# RF.net
KiCad netlist of a schematic drawn in Altium Designer
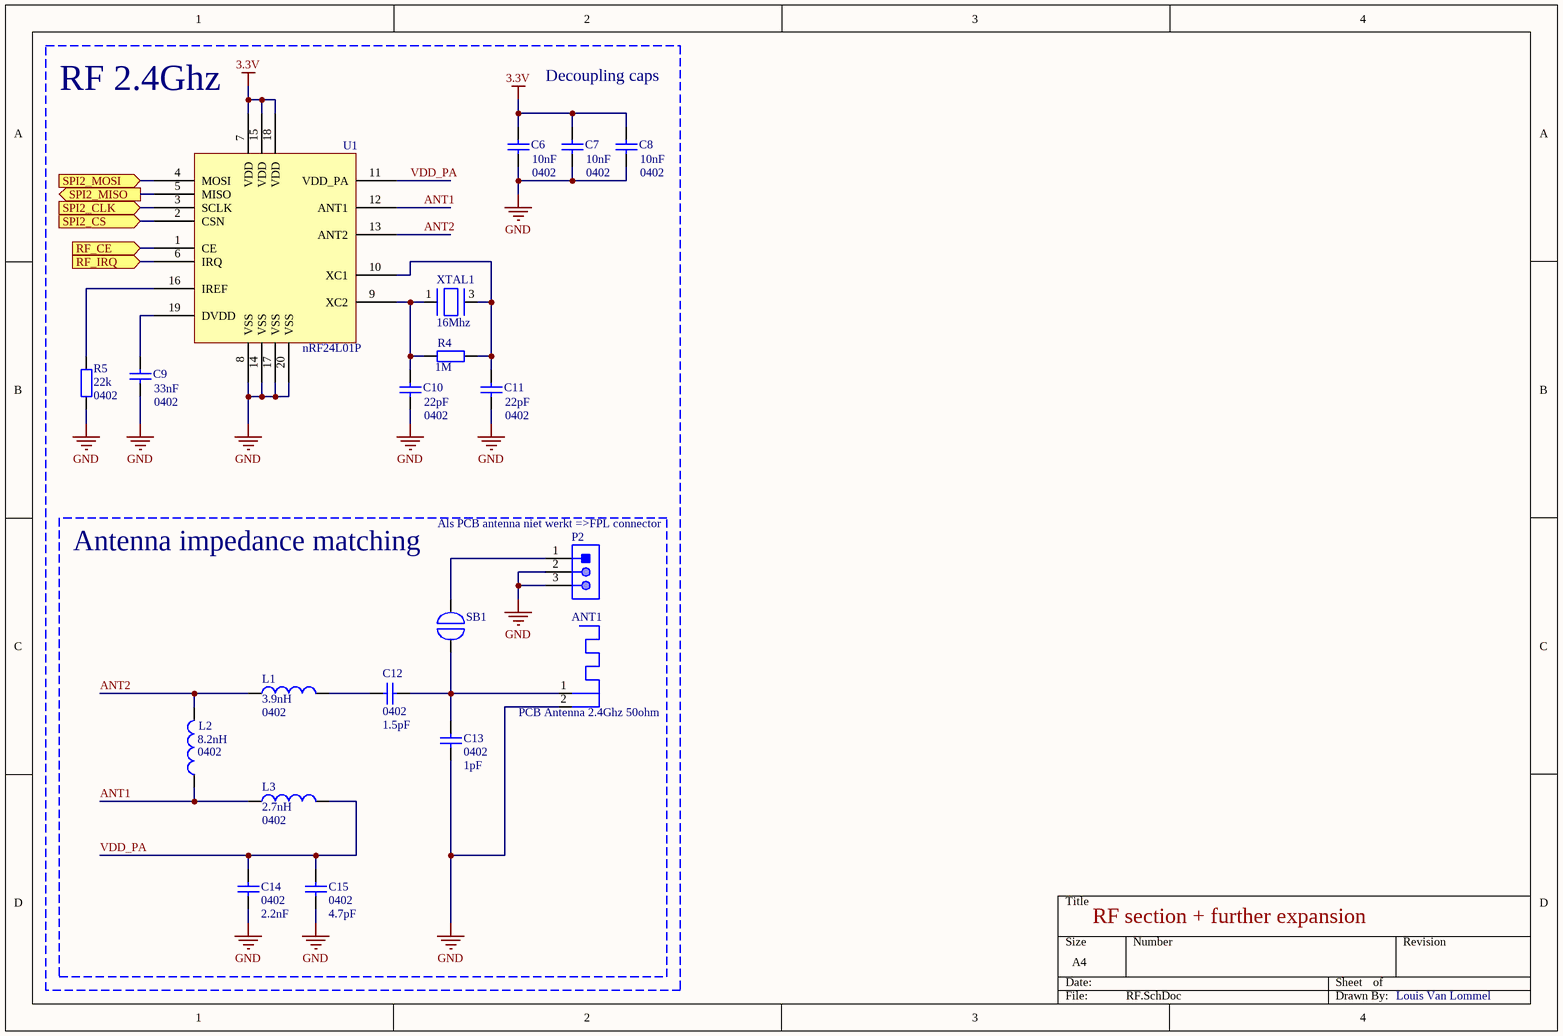
[diagram p0: RF.SchDoc]

(export (version "E")
  (design (tool "Eeschema 10.0.6"))
  (components
    (comp (ref "ANT1")
      (value "PCB Antenna 2.4Ghz 50ohm")
      (footprint "2.4Ghz Antenna")
      (libsource (lib "PE2_Schematics") (part "Antenna 2.4Ghz"))
    )
    (comp (ref "C6")
      (value "0402")
      (footprint "CAP_0402")
      (description "Capacitor")
      (fields (field (name "ALTIUM_VALUE") "10nF") (field (name "PUBLISHER") "Altium Limited"))
      (libsource (lib "Miscellaneous Devices") (part "Cap"))
    )
    (comp (ref "C7")
      (value "0402")
      (footprint "CAP_0402")
      (description "Capacitor")
      (fields (field (name "ALTIUM_VALUE") "10nF") (field (name "PUBLISHER") "Altium Limited"))
      (libsource (lib "Miscellaneous Devices") (part "Cap"))
    )
    (comp (ref "C8")
      (value "0402")
      (footprint "CAP_0402")
      (description "Capacitor")
      (fields (field (name "ALTIUM_VALUE") "10nF") (field (name "PUBLISHER") "Altium Limited"))
      (libsource (lib "Miscellaneous Devices") (part "Cap"))
    )
    (comp (ref "C9")
      (value "0402")
      (footprint "CAP_0402")
      (description "Capacitor")
      (fields (field (name "ALTIUM_VALUE") "33nF") (field (name "PUBLISHER") "Altium Limited"))
      (libsource (lib "Miscellaneous Devices") (part "Cap"))
    )
    (comp (ref "C10")
      (value "0402")
      (footprint "CAP_0402")
      (description "Capacitor")
      (fields (field (name "ALTIUM_VALUE") "22pF") (field (name "PUBLISHER") "Altium Limited"))
      (libsource (lib "Miscellaneous Devices") (part "Cap"))
    )
    (comp (ref "C11")
      (value "0402")
      (footprint "CAP_0402")
      (description "Capacitor")
      (fields (field (name "ALTIUM_VALUE") "22pF") (field (name "PUBLISHER") "Altium Limited"))
      (libsource (lib "Miscellaneous Devices") (part "Cap"))
    )
    (comp (ref "C12")
      (value "0402")
      (footprint "CAP_0402")
      (description "Capacitor")
      (fields (field (name "ALTIUM_VALUE") "1.5pF") (field (name "PUBLISHER") "Altium Limited"))
      (libsource (lib "Miscellaneous Devices") (part "Cap"))
    )
    (comp (ref "C13")
      (value "0402")
      (footprint "CAP_0402")
      (description "Capacitor")
      (fields (field (name "ALTIUM_VALUE") "1pF") (field (name "PUBLISHER") "Altium Limited"))
      (libsource (lib "Miscellaneous Devices") (part "Cap"))
    )
    (comp (ref "C14")
      (value "0402")
      (footprint "CAP_0402")
      (description "Capacitor")
      (fields (field (name "ALTIUM_VALUE") "2.2nF") (field (name "PUBLISHER") "Altium Limited"))
      (libsource (lib "Miscellaneous Devices") (part "Cap"))
    )
    (comp (ref "C15")
      (value "0402")
      (footprint "CAP_0402")
      (description "Capacitor")
      (fields (field (name "ALTIUM_VALUE") "4.7pF") (field (name "PUBLISHER") "Altium Limited"))
      (libsource (lib "Miscellaneous Devices") (part "Cap"))
    )
    (comp (ref "L1")
      (value "0402")
      (footprint "IND_0402")
      (description "Inductor")
      (fields (field (name "ALTIUM_VALUE") "3.9nH") (field (name "PUBLISHER") "Altium Limited"))
      (libsource (lib "Miscellaneous Devices") (part "Inductor"))
    )
    (comp (ref "L2")
      (value "0402")
      (footprint "IND_0402")
      (description "Inductor")
      (fields (field (name "ALTIUM_VALUE") "8.2nH") (field (name "PUBLISHER") "Altium Limited"))
      (libsource (lib "Miscellaneous Devices") (part "Inductor"))
    )
    (comp (ref "L3")
      (value "0402")
      (footprint "IND_0402")
      (description "Inductor")
      (fields (field (name "ALTIUM_VALUE") "2.7nH") (field (name "PUBLISHER") "Altium Limited"))
      (libsource (lib "Miscellaneous Devices") (part "Inductor"))
    )
    (comp (ref "P2")
      (value "~")
      (footprint "HRS-U.FL-R-SMT-3_V")
      (description "Ultra Small Coaxial Connector, 6 GHz, -40 to 90 degC, 3-Pin SMD, RoHS, Bulk")
      (fields (field (name "MANUFACTURER") "Hirose Electric"))
      (libsource (lib "Altium Content Vault") (part "CN-1P-M-R3"))
    )
    (comp (ref "R4")
      (value "1M")
      (footprint "RES_0402")
      (description "Resistor")
      (fields (field (name "PUBLISHER") "Altium Limited"))
      (libsource (lib "Miscellaneous Devices") (part "Res2"))
    )
    (comp (ref "R5")
      (value "0402")
      (footprint "RES_0603")
      (description "Resistor")
      (fields (field (name "ALTIUM_VALUE") "22k") (field (name "PUBLISHER") "Altium Limited"))
      (libsource (lib "") (part "Res2_1"))
    )
    (comp (ref "SB1")
      (value "~")
      (footprint "Solder bridge RF 0.254")
      (libsource (lib "PE2_Schematics") (part "Solder bridge"))
    )
    (comp (ref "U1")
      (value "nRF24L01P")
      (footprint "QFN20 4x4")
      (description "Single Chip Transceiver, 2.4 GHz, 60 mW, 1.9 to 3.6 V, -40 to 85 degC, 20-Pin QFN, RoHS, Tray")
      (libsource (lib "AP2112") (part "nRF24L01P"))
    )
    (comp (ref "XTAL1")
      (value "16Mhz")
      (footprint "16Mhz_Crystal")
      (description "Crystal, 16 MHz, SMD, 3.2mm x 2.5mm, 30 ppm, 18 pF, 30 ppm, 7M")
      (libsource (lib "AP2112") (part "Crystal"))
    )
  )
  (nets
    (net (code "1") (name "/ANT1") (class "Default")
      (node (ref "L2") (pin "1") (pinfunction "1_1") (pintype "passive"))
      (node (ref "L3") (pin "1") (pinfunction "1_1") (pintype "passive"))
      (node (ref "U1") (pin "12") (pinfunction "ANT1_12") (pintype "passive"))
    )
    (net (code "2") (name "/ANT2") (class "Default")
      (node (ref "L1") (pin "1") (pinfunction "1_1") (pintype "passive"))
      (node (ref "L2") (pin "2") (pinfunction "2_2") (pintype "passive"))
      (node (ref "U1") (pin "13") (pinfunction "ANT2_13") (pintype "passive"))
    )
    (net (code "3") (name "/RF_CE") (class "Default")
      (node (ref "U1") (pin "1") (pinfunction "CE_1") (pintype "passive"))
    )
    (net (code "4") (name "/RF_IRQ") (class "Default")
      (node (ref "U1") (pin "6") (pinfunction "IRQ_6") (pintype "passive"))
    )
    (net (code "5") (name "/SPI2_CLK") (class "Default")
      (node (ref "U1") (pin "3") (pinfunction "SCLK_3") (pintype "passive"))
    )
    (net (code "6") (name "/SPI2_CS") (class "Default")
      (node (ref "U1") (pin "2") (pinfunction "CSN_2") (pintype "passive"))
    )
    (net (code "7") (name "/SPI2_MISO") (class "Default")
      (node (ref "U1") (pin "5") (pinfunction "MISO_5") (pintype "passive"))
    )
    (net (code "8") (name "/SPI2_MOSI") (class "Default")
      (node (ref "U1") (pin "4") (pinfunction "MOSI_4") (pintype "passive"))
    )
    (net (code "9") (name "/VDD_PA") (class "Default")
      (node (ref "C14") (pin "1") (pinfunction "1_1") (pintype "passive"))
      (node (ref "C15") (pin "1") (pinfunction "1_1") (pintype "passive"))
      (node (ref "L3") (pin "2") (pinfunction "2_2") (pintype "passive"))
      (node (ref "U1") (pin "11") (pinfunction "VDD_PA_11") (pintype "passive"))
    )
    (net (code "10") (name "3.3V") (class "Default")
      (node (ref "C6") (pin "2") (pinfunction "2_2") (pintype "passive"))
      (node (ref "C7") (pin "2") (pinfunction "2_2") (pintype "passive"))
      (node (ref "C8") (pin "2") (pinfunction "2_2") (pintype "passive"))
      (node (ref "U1") (pin "15") (pinfunction "VDD_15") (pintype "passive"))
      (node (ref "U1") (pin "18") (pinfunction "VDD_18") (pintype "passive"))
      (node (ref "U1") (pin "7") (pinfunction "VDD_7") (pintype "passive"))
    )
    (net (code "11") (name "GND") (class "Default")
      (node (ref "ANT1") (pin "2") (pinfunction "GND_2") (pintype "passive"))
      (node (ref "C10") (pin "1") (pinfunction "1_1") (pintype "passive"))
      (node (ref "C11") (pin "1") (pinfunction "1_1") (pintype "passive"))
      (node (ref "C13") (pin "2") (pinfunction "2_2") (pintype "passive"))
      (node (ref "C14") (pin "2") (pinfunction "2_2") (pintype "passive"))
      (node (ref "C15") (pin "2") (pinfunction "2_2") (pintype "passive"))
      (node (ref "C6") (pin "1") (pinfunction "1_1") (pintype "passive"))
      (node (ref "C7") (pin "1") (pinfunction "1_1") (pintype "passive"))
      (node (ref "C8") (pin "1") (pinfunction "1_1") (pintype "passive"))
      (node (ref "C9") (pin "1") (pinfunction "1_1") (pintype "passive"))
      (node (ref "P2") (pin "2") (pinfunction "2_2") (pintype "passive"))
      (node (ref "P2") (pin "3") (pinfunction "3_3") (pintype "passive"))
      (node (ref "R5") (pin "2") (pinfunction "2_2") (pintype "passive"))
      (node (ref "U1") (pin "14") (pinfunction "VSS_14") (pintype "passive"))
      (node (ref "U1") (pin "17") (pinfunction "VSS_17") (pintype "passive"))
      (node (ref "U1") (pin "20") (pinfunction "VSS_20") (pintype "passive"))
      (node (ref "U1") (pin "8") (pinfunction "VSS_8") (pintype "passive"))
    )
    (net (code "12") (name "Net-(ANT1-RF)") (class "Default")
      (node (ref "ANT1") (pin "1") (pinfunction "RF_1") (pintype "passive"))
      (node (ref "C12") (pin "1") (pinfunction "1_1") (pintype "passive"))
      (node (ref "C13") (pin "1") (pinfunction "1_1") (pintype "passive"))
      (node (ref "SB1") (pin "3") (pinfunction "3_3") (pintype "passive"))
    )
    (net (code "13") (name "Net-(C12-Pad2)") (class "Default")
      (node (ref "C12") (pin "2") (pinfunction "2_2") (pintype "passive"))
      (node (ref "L1") (pin "2") (pinfunction "2_2") (pintype "passive"))
    )
    (net (code "14") (name "Net-(P2-Pad1)") (class "Default")
      (node (ref "P2") (pin "1") (pinfunction "1_1") (pintype "passive"))
      (node (ref "SB1") (pin "4") (pinfunction "4_4") (pintype "passive"))
    )
    (net (code "15") (name "Net-(U1-DVDD)") (class "Default")
      (node (ref "C9") (pin "2") (pinfunction "2_2") (pintype "passive"))
      (node (ref "U1") (pin "19") (pinfunction "DVDD_19") (pintype "passive"))
    )
    (net (code "16") (name "Net-(U1-IREF)") (class "Default")
      (node (ref "R5") (pin "1") (pinfunction "1_1") (pintype "passive"))
      (node (ref "U1") (pin "16") (pinfunction "IREF_16") (pintype "passive"))
    )
    (net (code "17") (name "Net-(U1-XC1)") (class "Default")
      (node (ref "C11") (pin "2") (pinfunction "2_2") (pintype "passive"))
      (node (ref "R4") (pin "2") (pinfunction "2_2") (pintype "passive"))
      (node (ref "U1") (pin "10") (pinfunction "XC1_10") (pintype "passive"))
      (node (ref "XTAL1") (pin "3") (pinfunction "3_3") (pintype "passive"))
    )
    (net (code "18") (name "Net-(U1-XC2)") (class "Default")
      (node (ref "C10") (pin "2") (pinfunction "2_2") (pintype "passive"))
      (node (ref "R4") (pin "1") (pinfunction "1_1") (pintype "passive"))
      (node (ref "U1") (pin "9") (pinfunction "XC2_9") (pintype "passive"))
      (node (ref "XTAL1") (pin "1") (pinfunction "1_1") (pintype "passive"))
    )
  )
)
